# WS2811-Multi_Ver110_20211128.net
KiCad netlist of a schematic drawn in EAGLE
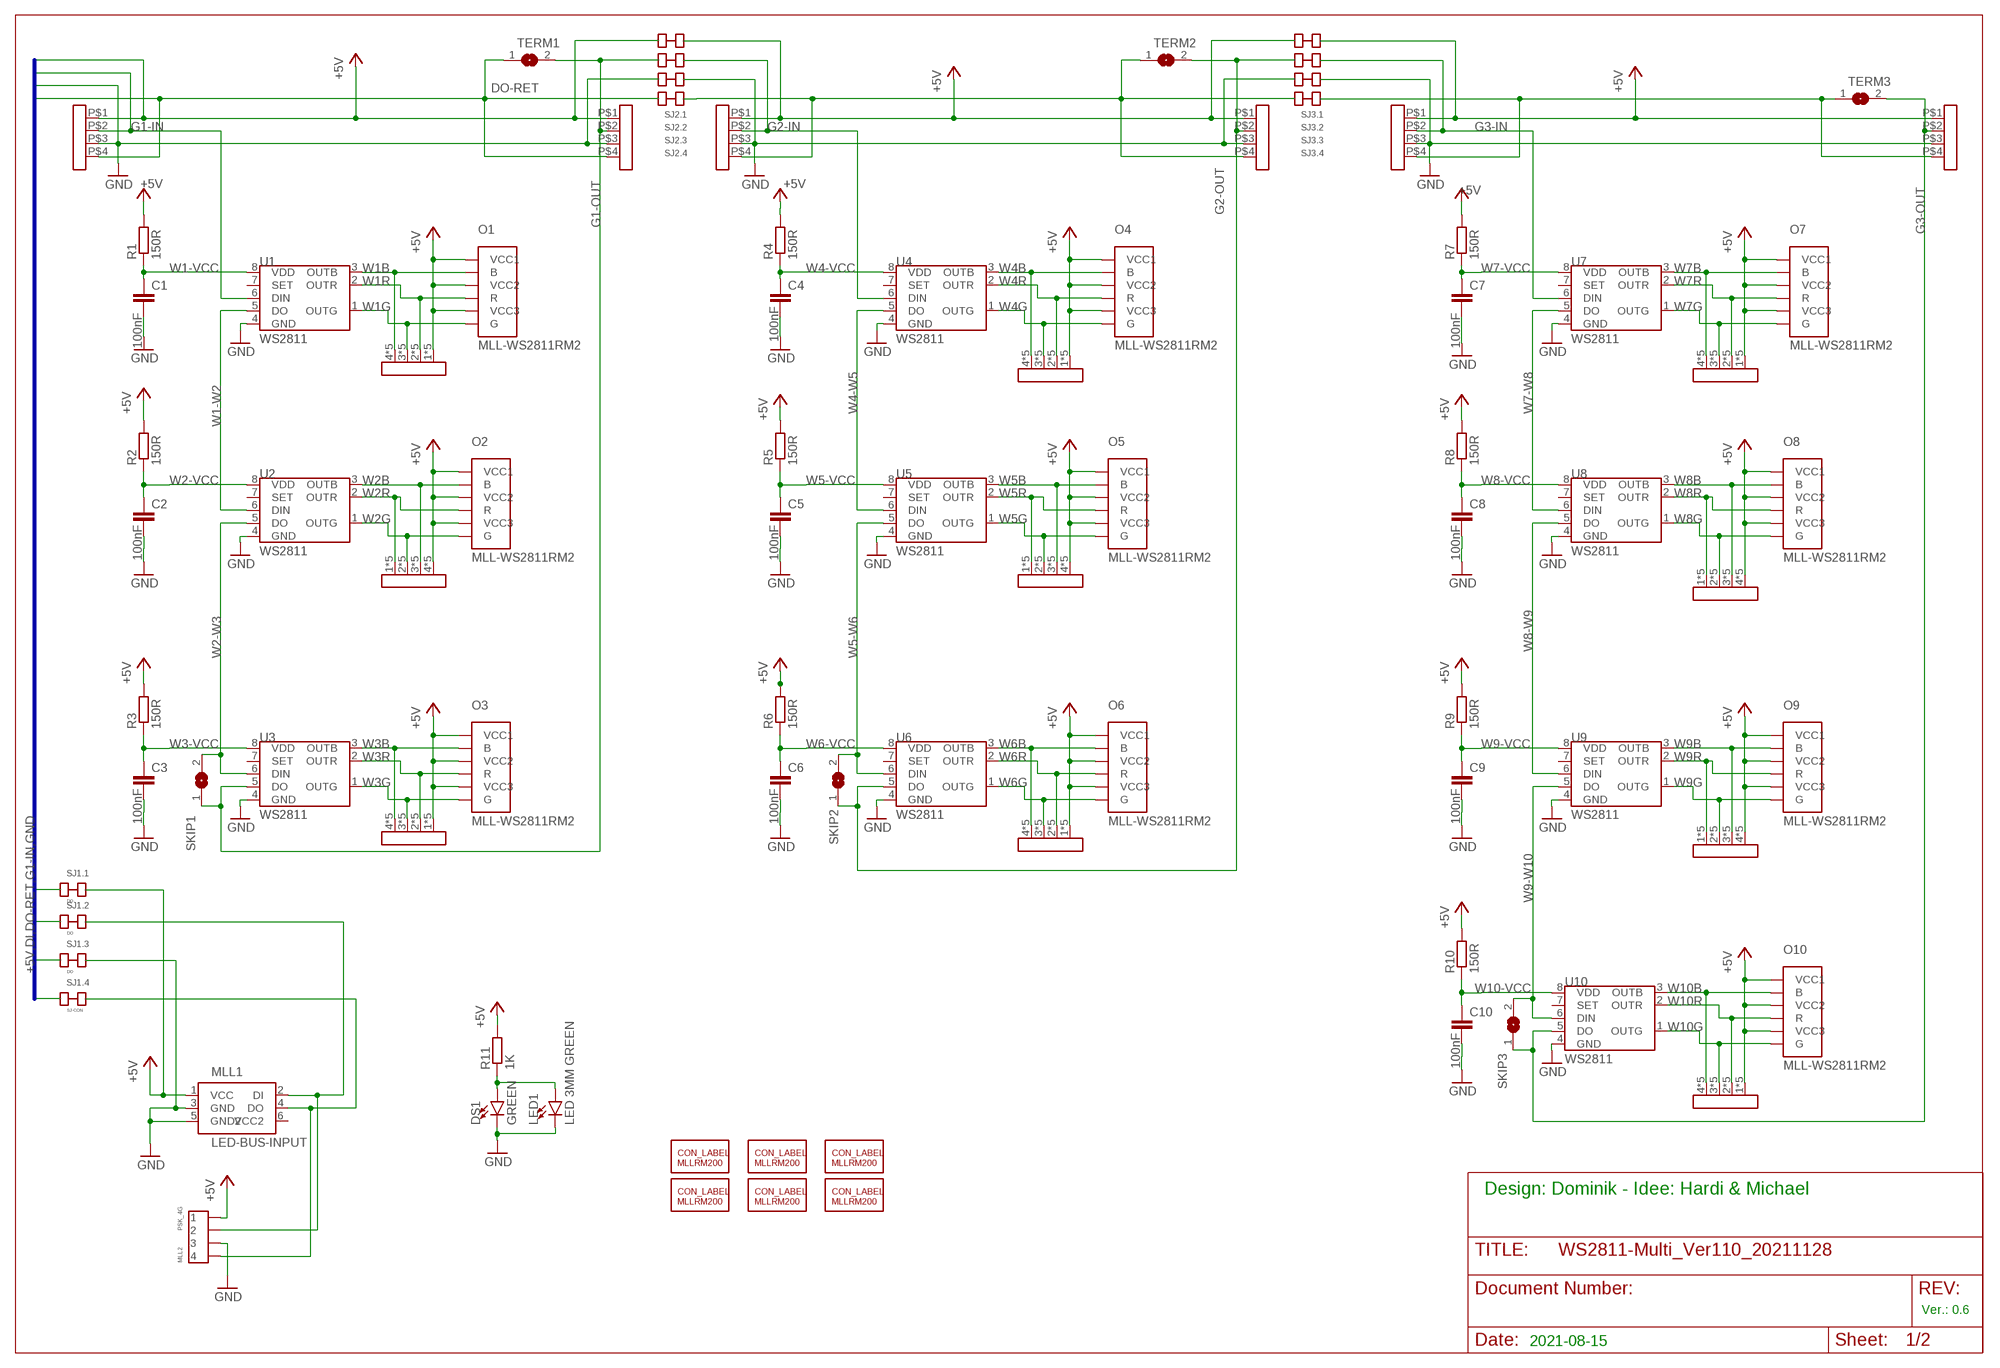
[diagram p0: schematic, sheet 1]
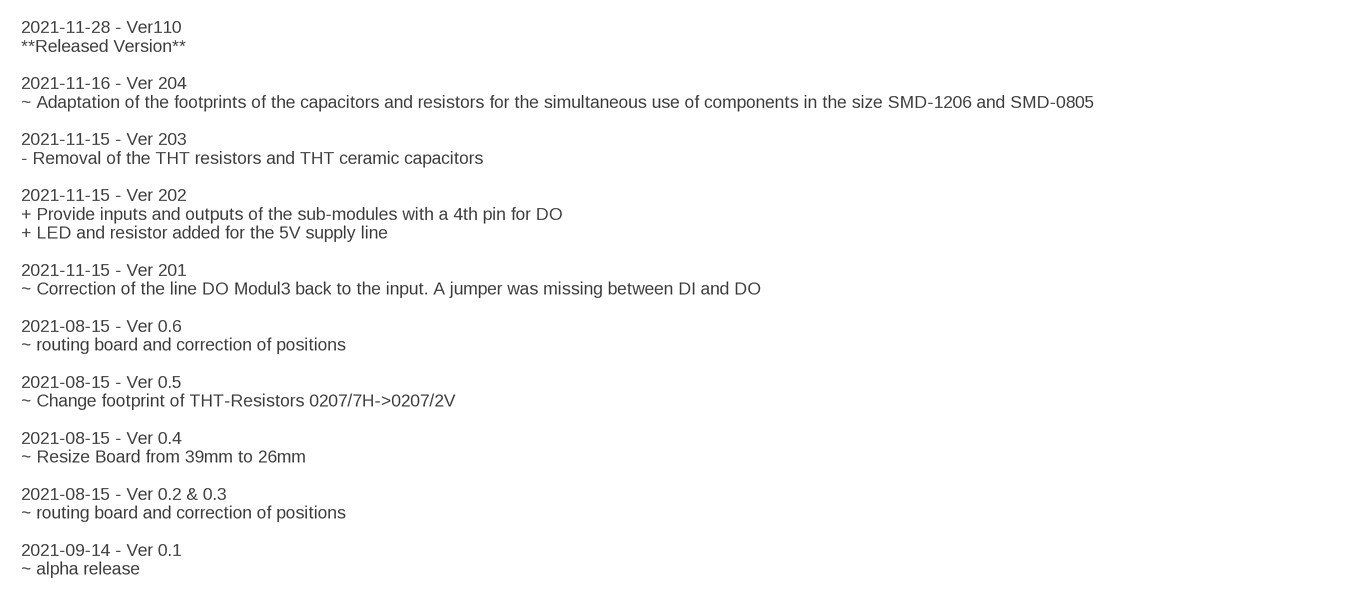
[diagram p1: schematic, sheet 2]

(export (version "E")
  (design (tool "Eeschema 10.0.6"))
  (components
    (comp (ref "C1")
      (value "100nF")
      (footprint "eagle-import:C1206")
      (libsource (lib "eagle-import") (part "C-EUC1206"))
    )
    (comp (ref "C2")
      (value "100nF")
      (footprint "eagle-import:C1206")
      (libsource (lib "eagle-import") (part "C-EUC1206"))
    )
    (comp (ref "C3")
      (value "100nF")
      (footprint "eagle-import:C1206")
      (libsource (lib "eagle-import") (part "C-EUC1206"))
    )
    (comp (ref "C4")
      (value "100nF")
      (footprint "eagle-import:C1206")
      (libsource (lib "eagle-import") (part "C-EUC1206"))
    )
    (comp (ref "C5")
      (value "100nF")
      (footprint "eagle-import:C1206")
      (libsource (lib "eagle-import") (part "C-EUC1206"))
    )
    (comp (ref "C6")
      (value "100nF")
      (footprint "eagle-import:C1206")
      (libsource (lib "eagle-import") (part "C-EUC1206"))
    )
    (comp (ref "C7")
      (value "100nF")
      (footprint "eagle-import:C1206")
      (libsource (lib "eagle-import") (part "C-EUC1206"))
    )
    (comp (ref "C8")
      (value "100nF")
      (footprint "eagle-import:C1206")
      (libsource (lib "eagle-import") (part "C-EUC1206"))
    )
    (comp (ref "C9")
      (value "100nF")
      (footprint "eagle-import:C1206")
      (libsource (lib "eagle-import") (part "C-EUC1206"))
    )
    (comp (ref "C10")
      (value "100nF")
      (footprint "eagle-import:C1206")
      (libsource (lib "eagle-import") (part "C-EUC1206"))
    )
    (comp (ref "DS1")
      (value "GREEN")
      (footprint "eagle-import:LED-1206")
      (libsource (lib "eagle-import") (part "LED-GREEN1206"))
    )
    (comp (ref "LED1")
      (value "LED 3MM GREEN")
      (footprint "eagle-import:LED_3MM")
      (libsource (lib "eagle-import") (part "LED3MM"))
    )
    (comp (ref "M1_IN")
      (value "4XRM254")
      (footprint "eagle-import:4XRM254")
      (libsource (lib "eagle-import") (part "4XRM254"))
    )
    (comp (ref "M1_OUT")
      (value "4XRM254")
      (footprint "eagle-import:4XRM254")
      (libsource (lib "eagle-import") (part "4XRM254"))
    )
    (comp (ref "M2_IN")
      (value "4XRM254")
      (footprint "eagle-import:4XRM254")
      (libsource (lib "eagle-import") (part "4XRM254"))
    )
    (comp (ref "M2_OUT")
      (value "4XRM254")
      (footprint "eagle-import:4XRM254")
      (libsource (lib "eagle-import") (part "4XRM254"))
    )
    (comp (ref "M3_IN")
      (value "4XRM254")
      (footprint "eagle-import:4XRM254")
      (libsource (lib "eagle-import") (part "4XRM254"))
    )
    (comp (ref "M3_OUT")
      (value "4XRM254")
      (footprint "eagle-import:4XRM254")
      (libsource (lib "eagle-import") (part "4XRM254"))
    )
    (comp (ref "MLL1")
      (value "LED-BUS-INPUT")
      (footprint "eagle-import:IDC6")
      (libsource (lib "eagle-import") (part "LED-BUS-INPUT"))
    )
    (comp (ref "MLL2")
      (value "PSK_4G")
      (footprint "eagle-import:PSSG4")
      (libsource (lib "eagle-import") (part "PSK_4G"))
    )
    (comp (ref "O1")
      (value "MLL-WS2811RM2")
      (footprint "eagle-import:MLL-WS2811-RM2")
      (libsource (lib "eagle-import") (part "MLL-WS2811RM2"))
    )
    (comp (ref "O2")
      (value "MLL-WS2811RM2")
      (footprint "eagle-import:MLL-WS2811-RM2")
      (libsource (lib "eagle-import") (part "MLL-WS2811RM2"))
    )
    (comp (ref "O3")
      (value "MLL-WS2811RM2")
      (footprint "eagle-import:MLL-WS2811-RM2")
      (libsource (lib "eagle-import") (part "MLL-WS2811RM2"))
    )
    (comp (ref "O4")
      (value "MLL-WS2811RM2")
      (footprint "eagle-import:MLL-WS2811-RM2")
      (libsource (lib "eagle-import") (part "MLL-WS2811RM2"))
    )
    (comp (ref "O5")
      (value "MLL-WS2811RM2")
      (footprint "eagle-import:MLL-WS2811-RM2")
      (libsource (lib "eagle-import") (part "MLL-WS2811RM2"))
    )
    (comp (ref "O6")
      (value "MLL-WS2811RM2")
      (footprint "eagle-import:MLL-WS2811-RM2")
      (libsource (lib "eagle-import") (part "MLL-WS2811RM2"))
    )
    (comp (ref "O7")
      (value "MLL-WS2811RM2")
      (footprint "eagle-import:MLL-WS2811-RM2")
      (libsource (lib "eagle-import") (part "MLL-WS2811RM2"))
    )
    (comp (ref "O8")
      (value "MLL-WS2811RM2")
      (footprint "eagle-import:MLL-WS2811-RM2")
      (libsource (lib "eagle-import") (part "MLL-WS2811RM2"))
    )
    (comp (ref "O9")
      (value "MLL-WS2811RM2")
      (footprint "eagle-import:MLL-WS2811-RM2")
      (libsource (lib "eagle-import") (part "MLL-WS2811RM2"))
    )
    (comp (ref "O10")
      (value "MLL-WS2811RM2")
      (footprint "eagle-import:MLL-WS2811-RM2")
      (libsource (lib "eagle-import") (part "MLL-WS2811RM2"))
    )
    (comp (ref "R1")
      (value "150R")
      (footprint "eagle-import:R1206")
      (libsource (lib "eagle-import") (part "R-EU_R1206"))
    )
    (comp (ref "R2")
      (value "150R")
      (footprint "eagle-import:R1206")
      (libsource (lib "eagle-import") (part "R-EU_R1206"))
    )
    (comp (ref "R3")
      (value "150R")
      (footprint "eagle-import:R1206")
      (libsource (lib "eagle-import") (part "R-EU_R1206"))
    )
    (comp (ref "R4")
      (value "150R")
      (footprint "eagle-import:R1206")
      (libsource (lib "eagle-import") (part "R-EU_R1206"))
    )
    (comp (ref "R5")
      (value "150R")
      (footprint "eagle-import:R1206")
      (libsource (lib "eagle-import") (part "R-EU_R1206"))
    )
    (comp (ref "R6")
      (value "150R")
      (footprint "eagle-import:R1206")
      (libsource (lib "eagle-import") (part "R-EU_R1206"))
    )
    (comp (ref "R7")
      (value "150R")
      (footprint "eagle-import:R1206")
      (libsource (lib "eagle-import") (part "R-EU_R1206"))
    )
    (comp (ref "R8")
      (value "150R")
      (footprint "eagle-import:R1206")
      (libsource (lib "eagle-import") (part "R-EU_R1206"))
    )
    (comp (ref "R9")
      (value "150R")
      (footprint "eagle-import:R1206")
      (libsource (lib "eagle-import") (part "R-EU_R1206"))
    )
    (comp (ref "R10")
      (value "150R")
      (footprint "eagle-import:R1206")
      (libsource (lib "eagle-import") (part "R-EU_R1206"))
    )
    (comp (ref "R11")
      (value "1K")
      (footprint "eagle-import:R1206")
      (libsource (lib "eagle-import") (part "R-EU_R1206"))
    )
    (comp (ref "SJ1.1")
      (value "DO")
      (footprint "eagle-import:SJ-CON")
      (libsource (lib "eagle-import") (part "SJ-CON"))
    )
    (comp (ref "SJ1.2")
      (value "DO")
      (footprint "eagle-import:SJ-CON")
      (libsource (lib "eagle-import") (part "SJ-CON"))
    )
    (comp (ref "SJ1.3")
      (value "DO")
      (footprint "eagle-import:SJ-CON")
      (libsource (lib "eagle-import") (part "SJ-CON"))
    )
    (comp (ref "SJ1.4")
      (value "SJ-CON")
      (footprint "eagle-import:SJ-CON")
      (libsource (lib "eagle-import") (part "SJ-CON"))
    )
    (comp (ref "SJ2.1")
      (value "SJ-CON")
      (footprint "eagle-import:SJ-CON")
      (libsource (lib "eagle-import") (part "SJ-CON"))
    )
    (comp (ref "SJ2.2")
      (value "SJ-CON")
      (footprint "eagle-import:SJ-CON")
      (libsource (lib "eagle-import") (part "SJ-CON"))
    )
    (comp (ref "SJ2.3")
      (value "SJ-CON")
      (footprint "eagle-import:SJ-CON")
      (libsource (lib "eagle-import") (part "SJ-CON"))
    )
    (comp (ref "SJ2.4")
      (value "SJ-CON")
      (footprint "eagle-import:SJ-CON")
      (libsource (lib "eagle-import") (part "SJ-CON"))
    )
    (comp (ref "SJ3.1")
      (value "SJ-CON")
      (footprint "eagle-import:SJ-CON")
      (libsource (lib "eagle-import") (part "SJ-CON"))
    )
    (comp (ref "SJ3.2")
      (value "SJ-CON")
      (footprint "eagle-import:SJ-CON")
      (libsource (lib "eagle-import") (part "SJ-CON"))
    )
    (comp (ref "SJ3.3")
      (value "SJ-CON")
      (footprint "eagle-import:SJ-CON")
      (libsource (lib "eagle-import") (part "SJ-CON"))
    )
    (comp (ref "SJ3.4")
      (value "SJ-CON")
      (footprint "eagle-import:SJ-CON")
      (libsource (lib "eagle-import") (part "SJ-CON"))
    )
    (comp (ref "SKIP1")
      (value "SJ")
      (footprint "eagle-import:SJ")
      (libsource (lib "eagle-import") (part "SJ"))
    )
    (comp (ref "SKIP2")
      (value "SJ")
      (footprint "eagle-import:SJ")
      (libsource (lib "eagle-import") (part "SJ"))
    )
    (comp (ref "SKIP3")
      (value "SJ")
      (footprint "eagle-import:SJ")
      (libsource (lib "eagle-import") (part "SJ"))
    )
    (comp (ref "TERM1")
      (value "SJ")
      (footprint "eagle-import:SJ")
      (libsource (lib "eagle-import") (part "SJ"))
    )
    (comp (ref "TERM2")
      (value "SJ")
      (footprint "eagle-import:SJ")
      (libsource (lib "eagle-import") (part "SJ"))
    )
    (comp (ref "TERM3")
      (value "SJ")
      (footprint "eagle-import:SJ")
      (libsource (lib "eagle-import") (part "SJ"))
    )
    (comp (ref "U$1")
      (value "CON-LABEL_MLLRM200_2RGB_M")
      (footprint "eagle-import:CON-LABEL_MLLRM200_RGB_M")
      (libsource (lib "eagle-import") (part "CON-LABEL_MLLRM200_2RGB_M"))
    )
    (comp (ref "U$2")
      (value "CON-LABEL_MLLRM200")
      (footprint "eagle-import:CON-LABEL_MLLRM200")
      (libsource (lib "eagle-import") (part "CON-LABEL_MLLRM200"))
    )
    (comp (ref "U$3")
      (value "CON-LABEL_MLLRM200_2RGB_M")
      (footprint "eagle-import:CON-LABEL_MLLRM200_RGB_M")
      (libsource (lib "eagle-import") (part "CON-LABEL_MLLRM200_2RGB_M"))
    )
    (comp (ref "U$4")
      (value "CON-LABEL_MLLRM200_2RGB_M")
      (footprint "eagle-import:CON-LABEL_MLLRM200_RGB_M")
      (libsource (lib "eagle-import") (part "CON-LABEL_MLLRM200_2RGB_M"))
    )
    (comp (ref "U$5")
      (value "CON-LABEL_MLLRM200_2RGB")
      (footprint "eagle-import:CON-LABEL_MLLRM200_RGB")
      (libsource (lib "eagle-import") (part "CON-LABEL_MLLRM200_2RGB"))
    )
    (comp (ref "U$6")
      (value "CON-LABEL_MLLRM200")
      (footprint "eagle-import:CON-LABEL_MLLRM200")
      (libsource (lib "eagle-import") (part "CON-LABEL_MLLRM200"))
    )
    (comp (ref "U$7")
      (value "4XRM200LONG-NOH_DOUBLE")
      (footprint "eagle-import:4XRM200LONG_NOH_DOUBLE")
      (libsource (lib "eagle-import") (part "4XRM200LONG-NOH_DOUBLE"))
    )
    (comp (ref "U$8")
      (value "4XRM200LONG-NOH_DOUBLE")
      (footprint "eagle-import:4XRM200LONG_NOH_DOUBLE")
      (libsource (lib "eagle-import") (part "4XRM200LONG-NOH_DOUBLE"))
    )
    (comp (ref "U$9")
      (value "4XRM200LONG-NOH_DOUBLE")
      (footprint "eagle-import:4XRM200LONG_NOH_DOUBLE")
      (libsource (lib "eagle-import") (part "4XRM200LONG-NOH_DOUBLE"))
    )
    (comp (ref "U$14")
      (value "4XRM200LONG-NOH_DOUBLE")
      (footprint "eagle-import:4XRM200LONG_NOH_DOUBLE")
      (libsource (lib "eagle-import") (part "4XRM200LONG-NOH_DOUBLE"))
    )
    (comp (ref "U$15")
      (value "4XRM200LONG-NOH_DOUBLE")
      (footprint "eagle-import:4XRM200LONG_NOH_DOUBLE")
      (libsource (lib "eagle-import") (part "4XRM200LONG-NOH_DOUBLE"))
    )
    (comp (ref "U$16")
      (value "4XRM200LONG-NOH_DOUBLE")
      (footprint "eagle-import:4XRM200LONG_NOH_DOUBLE")
      (libsource (lib "eagle-import") (part "4XRM200LONG-NOH_DOUBLE"))
    )
    (comp (ref "U$17")
      (value "4XRM200LONG-NOH_DOUBLE")
      (footprint "eagle-import:4XRM200LONG_NOH_DOUBLE")
      (libsource (lib "eagle-import") (part "4XRM200LONG-NOH_DOUBLE"))
    )
    (comp (ref "U$18")
      (value "4XRM200LONG-NOH_DOUBLE")
      (footprint "eagle-import:4XRM200LONG_NOH_DOUBLE")
      (libsource (lib "eagle-import") (part "4XRM200LONG-NOH_DOUBLE"))
    )
    (comp (ref "U$19")
      (value "4XRM200LONG-NOH_DOUBLE")
      (footprint "eagle-import:4XRM200LONG_NOH_DOUBLE")
      (libsource (lib "eagle-import") (part "4XRM200LONG-NOH_DOUBLE"))
    )
    (comp (ref "U$20")
      (value "4XRM200LONG-NOH_DOUBLE")
      (footprint "eagle-import:4XRM200LONG_NOH_DOUBLE")
      (libsource (lib "eagle-import") (part "4XRM200LONG-NOH_DOUBLE"))
    )
    (comp (ref "U1")
      (value "WS2811")
      (footprint "eagle-import:SOP8")
      (libsource (lib "eagle-import") (part "WS2811-ICSOP8"))
    )
    (comp (ref "U2")
      (value "WS2811")
      (footprint "eagle-import:SOP8")
      (libsource (lib "eagle-import") (part "WS2811-ICSOP8"))
    )
    (comp (ref "U3")
      (value "WS2811")
      (footprint "eagle-import:SOP8")
      (libsource (lib "eagle-import") (part "WS2811-ICSOP8"))
    )
    (comp (ref "U4")
      (value "WS2811")
      (footprint "eagle-import:SOP8")
      (libsource (lib "eagle-import") (part "WS2811-ICSOP8"))
    )
    (comp (ref "U5")
      (value "WS2811")
      (footprint "eagle-import:SOP8")
      (libsource (lib "eagle-import") (part "WS2811-ICSOP8"))
    )
    (comp (ref "U6")
      (value "WS2811")
      (footprint "eagle-import:SOP8")
      (libsource (lib "eagle-import") (part "WS2811-ICSOP8"))
    )
    (comp (ref "U7")
      (value "WS2811")
      (footprint "eagle-import:SOP8")
      (libsource (lib "eagle-import") (part "WS2811-ICSOP8"))
    )
    (comp (ref "U8")
      (value "WS2811")
      (footprint "eagle-import:SOP8")
      (libsource (lib "eagle-import") (part "WS2811-ICSOP8"))
    )
    (comp (ref "U9")
      (value "WS2811")
      (footprint "eagle-import:SOP8")
      (libsource (lib "eagle-import") (part "WS2811-ICSOP8"))
    )
    (comp (ref "U10")
      (value "WS2811")
      (footprint "eagle-import:SOP8")
      (libsource (lib "eagle-import") (part "WS2811-ICSOP8"))
    )
  )
  (nets
    (net (code "2") (name "+5V") (class "Default")
      (node (ref "M1_IN") (pin "P$1") (pinfunction "P$1_P$1") (pintype "bidirectional"))
      (node (ref "M1_OUT") (pin "P$1") (pinfunction "P$1_P$1") (pintype "bidirectional"))
      (node (ref "M2_IN") (pin "P$1") (pinfunction "P$1_P$1") (pintype "bidirectional"))
      (node (ref "M2_OUT") (pin "P$1") (pinfunction "P$1_P$1") (pintype "bidirectional"))
      (node (ref "M3_IN") (pin "P$1") (pinfunction "P$1_P$1") (pintype "bidirectional"))
      (node (ref "M3_OUT") (pin "P$1") (pinfunction "P$1_P$1") (pintype "bidirectional"))
      (node (ref "MLL1") (pin "1") (pinfunction "VCC_1") (pintype "power_in"))
      (node (ref "MLL2") (pin "P$1") (pinfunction "1_P$1") (pintype "bidirectional"))
      (node (ref "O1") (pin "VCC1") (pinfunction "VCC1_VCC1") (pintype "bidirectional"))
      (node (ref "O1") (pin "VCC2") (pinfunction "VCC2_VCC2") (pintype "bidirectional"))
      (node (ref "O1") (pin "VCC3") (pinfunction "VCC3_VCC3") (pintype "bidirectional"))
      (node (ref "O10") (pin "VCC1") (pinfunction "VCC1_VCC1") (pintype "bidirectional"))
      (node (ref "O10") (pin "VCC2") (pinfunction "VCC2_VCC2") (pintype "bidirectional"))
      (node (ref "O10") (pin "VCC3") (pinfunction "VCC3_VCC3") (pintype "bidirectional"))
      (node (ref "O2") (pin "VCC1") (pinfunction "VCC1_VCC1") (pintype "bidirectional"))
      (node (ref "O2") (pin "VCC2") (pinfunction "VCC2_VCC2") (pintype "bidirectional"))
      (node (ref "O2") (pin "VCC3") (pinfunction "VCC3_VCC3") (pintype "bidirectional"))
      (node (ref "O3") (pin "VCC1") (pinfunction "VCC1_VCC1") (pintype "bidirectional"))
      (node (ref "O3") (pin "VCC2") (pinfunction "VCC2_VCC2") (pintype "bidirectional"))
      (node (ref "O3") (pin "VCC3") (pinfunction "VCC3_VCC3") (pintype "bidirectional"))
      (node (ref "O4") (pin "VCC1") (pinfunction "VCC1_VCC1") (pintype "bidirectional"))
      (node (ref "O4") (pin "VCC2") (pinfunction "VCC2_VCC2") (pintype "bidirectional"))
      (node (ref "O4") (pin "VCC3") (pinfunction "VCC3_VCC3") (pintype "bidirectional"))
      (node (ref "O5") (pin "VCC1") (pinfunction "VCC1_VCC1") (pintype "bidirectional"))
      (node (ref "O5") (pin "VCC2") (pinfunction "VCC2_VCC2") (pintype "bidirectional"))
      (node (ref "O5") (pin "VCC3") (pinfunction "VCC3_VCC3") (pintype "bidirectional"))
      (node (ref "O6") (pin "VCC1") (pinfunction "VCC1_VCC1") (pintype "bidirectional"))
      (node (ref "O6") (pin "VCC2") (pinfunction "VCC2_VCC2") (pintype "bidirectional"))
      (node (ref "O6") (pin "VCC3") (pinfunction "VCC3_VCC3") (pintype "bidirectional"))
      (node (ref "O7") (pin "VCC1") (pinfunction "VCC1_VCC1") (pintype "bidirectional"))
      (node (ref "O7") (pin "VCC2") (pinfunction "VCC2_VCC2") (pintype "bidirectional"))
      (node (ref "O7") (pin "VCC3") (pinfunction "VCC3_VCC3") (pintype "bidirectional"))
      (node (ref "O8") (pin "VCC1") (pinfunction "VCC1_VCC1") (pintype "bidirectional"))
      (node (ref "O8") (pin "VCC2") (pinfunction "VCC2_VCC2") (pintype "bidirectional"))
      (node (ref "O8") (pin "VCC3") (pinfunction "VCC3_VCC3") (pintype "bidirectional"))
      (node (ref "O9") (pin "VCC1") (pinfunction "VCC1_VCC1") (pintype "bidirectional"))
      (node (ref "O9") (pin "VCC2") (pinfunction "VCC2_VCC2") (pintype "bidirectional"))
      (node (ref "O9") (pin "VCC3") (pinfunction "VCC3_VCC3") (pintype "bidirectional"))
      (node (ref "R1") (pin "2") (pinfunction "2_2") (pintype "passive"))
      (node (ref "R10") (pin "2") (pinfunction "2_2") (pintype "passive"))
      (node (ref "R11") (pin "2") (pinfunction "2_2") (pintype "passive"))
      (node (ref "R2") (pin "2") (pinfunction "2_2") (pintype "passive"))
      (node (ref "R3") (pin "2") (pinfunction "2_2") (pintype "passive"))
      (node (ref "R4") (pin "2") (pinfunction "2_2") (pintype "passive"))
      (node (ref "R5") (pin "2") (pinfunction "2_2") (pintype "passive"))
      (node (ref "R6") (pin "2") (pinfunction "2_2") (pintype "passive"))
      (node (ref "R7") (pin "2") (pinfunction "2_2") (pintype "passive"))
      (node (ref "R8") (pin "2") (pinfunction "2_2") (pintype "passive"))
      (node (ref "R9") (pin "2") (pinfunction "2_2") (pintype "passive"))
      (node (ref "SJ1.1") (pin "P$1") (pinfunction "P$1_P$1") (pintype "bidirectional"))
      (node (ref "SJ1.1") (pin "P$2") (pinfunction "P$2_P$2") (pintype "bidirectional"))
      (node (ref "SJ2.1") (pin "P$1") (pinfunction "P$1_P$1") (pintype "bidirectional"))
      (node (ref "SJ2.1") (pin "P$2") (pinfunction "P$2_P$2") (pintype "bidirectional"))
      (node (ref "SJ3.1") (pin "P$1") (pinfunction "P$1_P$1") (pintype "bidirectional"))
      (node (ref "SJ3.1") (pin "P$2") (pinfunction "P$2_P$2") (pintype "bidirectional"))
      (node (ref "U$14") (pin "1") (pinfunction "P$1_1") (pintype "bidirectional"))
      (node (ref "U$14") (pin "11") (pinfunction "P$1_11") (pintype "bidirectional"))
      (node (ref "U$14") (pin "12") (pinfunction "P$1_12") (pintype "bidirectional"))
      (node (ref "U$14") (pin "13") (pinfunction "P$1_13") (pintype "bidirectional"))
      (node (ref "U$14") (pin "1B") (pinfunction "P$1_1B") (pintype "bidirectional"))
      (node (ref "U$15") (pin "4") (pinfunction "P$4_4") (pintype "bidirectional"))
      (node (ref "U$15") (pin "41") (pinfunction "P$4_41") (pintype "bidirectional"))
      (node (ref "U$15") (pin "42") (pinfunction "P$4_42") (pintype "bidirectional"))
      (node (ref "U$15") (pin "43") (pinfunction "P$4_43") (pintype "bidirectional"))
      (node (ref "U$15") (pin "4B") (pinfunction "P$4_4B") (pintype "bidirectional"))
      (node (ref "U$16") (pin "1") (pinfunction "P$1_1") (pintype "bidirectional"))
      (node (ref "U$16") (pin "11") (pinfunction "P$1_11") (pintype "bidirectional"))
      (node (ref "U$16") (pin "12") (pinfunction "P$1_12") (pintype "bidirectional"))
      (node (ref "U$16") (pin "13") (pinfunction "P$1_13") (pintype "bidirectional"))
      (node (ref "U$16") (pin "1B") (pinfunction "P$1_1B") (pintype "bidirectional"))
      (node (ref "U$17") (pin "1") (pinfunction "P$1_1") (pintype "bidirectional"))
      (node (ref "U$17") (pin "11") (pinfunction "P$1_11") (pintype "bidirectional"))
      (node (ref "U$17") (pin "12") (pinfunction "P$1_12") (pintype "bidirectional"))
      (node (ref "U$17") (pin "13") (pinfunction "P$1_13") (pintype "bidirectional"))
      (node (ref "U$17") (pin "1B") (pinfunction "P$1_1B") (pintype "bidirectional"))
      (node (ref "U$18") (pin "4") (pinfunction "P$4_4") (pintype "bidirectional"))
      (node (ref "U$18") (pin "41") (pinfunction "P$4_41") (pintype "bidirectional"))
      (node (ref "U$18") (pin "42") (pinfunction "P$4_42") (pintype "bidirectional"))
      (node (ref "U$18") (pin "43") (pinfunction "P$4_43") (pintype "bidirectional"))
      (node (ref "U$18") (pin "4B") (pinfunction "P$4_4B") (pintype "bidirectional"))
      (node (ref "U$19") (pin "4") (pinfunction "P$4_4") (pintype "bidirectional"))
      (node (ref "U$19") (pin "41") (pinfunction "P$4_41") (pintype "bidirectional"))
      (node (ref "U$19") (pin "42") (pinfunction "P$4_42") (pintype "bidirectional"))
      (node (ref "U$19") (pin "43") (pinfunction "P$4_43") (pintype "bidirectional"))
      (node (ref "U$19") (pin "4B") (pinfunction "P$4_4B") (pintype "bidirectional"))
      (node (ref "U$20") (pin "1") (pinfunction "P$1_1") (pintype "bidirectional"))
      (node (ref "U$20") (pin "11") (pinfunction "P$1_11") (pintype "bidirectional"))
      (node (ref "U$20") (pin "12") (pinfunction "P$1_12") (pintype "bidirectional"))
      (node (ref "U$20") (pin "13") (pinfunction "P$1_13") (pintype "bidirectional"))
      (node (ref "U$20") (pin "1B") (pinfunction "P$1_1B") (pintype "bidirectional"))
      (node (ref "U$7") (pin "1") (pinfunction "P$1_1") (pintype "bidirectional"))
      (node (ref "U$7") (pin "11") (pinfunction "P$1_11") (pintype "bidirectional"))
      (node (ref "U$7") (pin "12") (pinfunction "P$1_12") (pintype "bidirectional"))
      (node (ref "U$7") (pin "13") (pinfunction "P$1_13") (pintype "bidirectional"))
      (node (ref "U$7") (pin "1B") (pinfunction "P$1_1B") (pintype "bidirectional"))
      (node (ref "U$8") (pin "4") (pinfunction "P$4_4") (pintype "bidirectional"))
      (node (ref "U$8") (pin "41") (pinfunction "P$4_41") (pintype "bidirectional"))
      (node (ref "U$8") (pin "42") (pinfunction "P$4_42") (pintype "bidirectional"))
      (node (ref "U$8") (pin "43") (pinfunction "P$4_43") (pintype "bidirectional"))
      (node (ref "U$8") (pin "4B") (pinfunction "P$4_4B") (pintype "bidirectional"))
      (node (ref "U$9") (pin "1") (pinfunction "P$1_1") (pintype "bidirectional"))
      (node (ref "U$9") (pin "11") (pinfunction "P$1_11") (pintype "bidirectional"))
      (node (ref "U$9") (pin "12") (pinfunction "P$1_12") (pintype "bidirectional"))
      (node (ref "U$9") (pin "13") (pinfunction "P$1_13") (pintype "bidirectional"))
      (node (ref "U$9") (pin "1B") (pinfunction "P$1_1B") (pintype "bidirectional"))
    )
    (net (code "4") (name "DO-RET") (class "Default")
      (node (ref "M1_IN") (pin "P$4") (pinfunction "P$4_P$4") (pintype "bidirectional"))
      (node (ref "M1_OUT") (pin "P$4") (pinfunction "P$4_P$4") (pintype "bidirectional"))
      (node (ref "SJ1.4") (pin "P$1") (pinfunction "P$1_P$1") (pintype "bidirectional"))
      (node (ref "SJ2.4") (pin "P$1") (pinfunction "P$1_P$1") (pintype "bidirectional"))
      (node (ref "TERM1") (pin "1") (pinfunction "1_1") (pintype "passive"))
    )
    (net (code "5") (name "G1-IN") (class "Default")
      (node (ref "M1_IN") (pin "P$2") (pinfunction "P$2_P$2") (pintype "bidirectional"))
      (node (ref "SJ1.2") (pin "P$1") (pinfunction "P$1_P$1") (pintype "bidirectional"))
      (node (ref "U1") (pin "6") (pinfunction "DIN_6") (pintype "input"))
    )
    (net (code "6") (name "G1-OUT") (class "Default")
      (node (ref "M1_OUT") (pin "P$2") (pinfunction "P$2_P$2") (pintype "bidirectional"))
      (node (ref "SJ2.2") (pin "P$1") (pinfunction "P$1_P$1") (pintype "bidirectional"))
      (node (ref "SKIP1") (pin "1") (pinfunction "1_1") (pintype "passive"))
      (node (ref "TERM1") (pin "2") (pinfunction "2_2") (pintype "passive"))
      (node (ref "U3") (pin "5") (pinfunction "DO_5") (pintype "output"))
    )
    (net (code "7") (name "G2-IN") (class "Default")
      (node (ref "M2_IN") (pin "P$2") (pinfunction "P$2_P$2") (pintype "bidirectional"))
      (node (ref "SJ2.2") (pin "P$2") (pinfunction "P$2_P$2") (pintype "bidirectional"))
      (node (ref "U4") (pin "6") (pinfunction "DIN_6") (pintype "input"))
    )
    (net (code "8") (name "G2-OUT") (class "Default")
      (node (ref "M2_OUT") (pin "P$2") (pinfunction "P$2_P$2") (pintype "bidirectional"))
      (node (ref "SJ3.2") (pin "P$1") (pinfunction "P$1_P$1") (pintype "bidirectional"))
      (node (ref "SKIP2") (pin "1") (pinfunction "1_1") (pintype "passive"))
      (node (ref "TERM2") (pin "2") (pinfunction "2_2") (pintype "passive"))
      (node (ref "U6") (pin "5") (pinfunction "DO_5") (pintype "output"))
    )
    (net (code "9") (name "G3-IN") (class "Default")
      (node (ref "M3_IN") (pin "P$2") (pinfunction "P$2_P$2") (pintype "bidirectional"))
      (node (ref "SJ3.2") (pin "P$2") (pinfunction "P$2_P$2") (pintype "bidirectional"))
      (node (ref "U7") (pin "6") (pinfunction "DIN_6") (pintype "input"))
    )
    (net (code "10") (name "G3-OUT") (class "Default")
      (node (ref "M3_OUT") (pin "P$2") (pinfunction "P$2_P$2") (pintype "bidirectional"))
      (node (ref "SKIP3") (pin "1") (pinfunction "1_1") (pintype "passive"))
      (node (ref "TERM3") (pin "2") (pinfunction "2_2") (pintype "passive"))
      (node (ref "U10") (pin "5") (pinfunction "DO_5") (pintype "output"))
    )
    (net (code "11") (name "GND") (class "Default")
      (node (ref "C1") (pin "2") (pinfunction "2_2") (pintype "passive"))
      (node (ref "C10") (pin "2") (pinfunction "2_2") (pintype "passive"))
      (node (ref "C2") (pin "2") (pinfunction "2_2") (pintype "passive"))
      (node (ref "C3") (pin "2") (pinfunction "2_2") (pintype "passive"))
      (node (ref "C4") (pin "2") (pinfunction "2_2") (pintype "passive"))
      (node (ref "C5") (pin "2") (pinfunction "2_2") (pintype "passive"))
      (node (ref "C6") (pin "2") (pinfunction "2_2") (pintype "passive"))
      (node (ref "C7") (pin "2") (pinfunction "2_2") (pintype "passive"))
      (node (ref "C8") (pin "2") (pinfunction "2_2") (pintype "passive"))
      (node (ref "C9") (pin "2") (pinfunction "2_2") (pintype "passive"))
      (node (ref "DS1") (pin "C") (pinfunction "C_C") (pintype "passive"))
      (node (ref "LED1") (pin "K") (pinfunction "C_K") (pintype "passive"))
      (node (ref "M1_IN") (pin "P$3") (pinfunction "P$3_P$3") (pintype "bidirectional"))
      (node (ref "M1_OUT") (pin "P$3") (pinfunction "P$3_P$3") (pintype "bidirectional"))
      (node (ref "M2_IN") (pin "P$3") (pinfunction "P$3_P$3") (pintype "bidirectional"))
      (node (ref "M2_OUT") (pin "P$3") (pinfunction "P$3_P$3") (pintype "bidirectional"))
      (node (ref "M3_IN") (pin "P$3") (pinfunction "P$3_P$3") (pintype "bidirectional"))
      (node (ref "M3_OUT") (pin "P$3") (pinfunction "P$3_P$3") (pintype "bidirectional"))
      (node (ref "MLL1") (pin "3") (pinfunction "GND_3") (pintype "power_in"))
      (node (ref "MLL1") (pin "5") (pinfunction "GND2_5") (pintype "power_in"))
      (node (ref "MLL2") (pin "P$3") (pinfunction "3_P$3") (pintype "bidirectional"))
      (node (ref "SJ1.3") (pin "P$1") (pinfunction "P$1_P$1") (pintype "bidirectional"))
      (node (ref "SJ1.3") (pin "P$2") (pinfunction "P$2_P$2") (pintype "bidirectional"))
      (node (ref "SJ2.3") (pin "P$1") (pinfunction "P$1_P$1") (pintype "bidirectional"))
      (node (ref "SJ2.3") (pin "P$2") (pinfunction "P$2_P$2") (pintype "bidirectional"))
      (node (ref "SJ3.3") (pin "P$1") (pinfunction "P$1_P$1") (pintype "bidirectional"))
      (node (ref "SJ3.3") (pin "P$2") (pinfunction "P$2_P$2") (pintype "bidirectional"))
      (node (ref "U1") (pin "4") (pinfunction "GND_4") (pintype "power_in"))
      (node (ref "U10") (pin "4") (pinfunction "GND_4") (pintype "power_in"))
      (node (ref "U2") (pin "4") (pinfunction "GND_4") (pintype "power_in"))
      (node (ref "U3") (pin "4") (pinfunction "GND_4") (pintype "power_in"))
      (node (ref "U4") (pin "4") (pinfunction "GND_4") (pintype "power_in"))
      (node (ref "U5") (pin "4") (pinfunction "GND_4") (pintype "power_in"))
      (node (ref "U6") (pin "4") (pinfunction "GND_4") (pintype "power_in"))
      (node (ref "U7") (pin "4") (pinfunction "GND_4") (pintype "power_in"))
      (node (ref "U8") (pin "4") (pinfunction "GND_4") (pintype "power_in"))
      (node (ref "U9") (pin "4") (pinfunction "GND_4") (pintype "power_in"))
    )
    (net (code "12") (name "Net-(DS1-PadA)") (class "Default")
      (node (ref "DS1") (pin "A") (pinfunction "A_A") (pintype "passive"))
      (node (ref "LED1") (pin "A") (pinfunction "A_A") (pintype "passive"))
      (node (ref "R11") (pin "1") (pinfunction "1_1") (pintype "passive"))
    )
    (net (code "13") (name "Net-(M2_IN-PadP$4)") (class "Default")
      (node (ref "M2_IN") (pin "P$4") (pinfunction "P$4_P$4") (pintype "bidirectional"))
      (node (ref "M2_OUT") (pin "P$4") (pinfunction "P$4_P$4") (pintype "bidirectional"))
      (node (ref "SJ2.4") (pin "P$2") (pinfunction "P$2_P$2") (pintype "bidirectional"))
      (node (ref "SJ3.4") (pin "P$1") (pinfunction "P$1_P$1") (pintype "bidirectional"))
      (node (ref "TERM2") (pin "1") (pinfunction "1_1") (pintype "passive"))
    )
    (net (code "14") (name "Net-(M3_IN-PadP$4)") (class "Default")
      (node (ref "M3_IN") (pin "P$4") (pinfunction "P$4_P$4") (pintype "bidirectional"))
      (node (ref "M3_OUT") (pin "P$4") (pinfunction "P$4_P$4") (pintype "bidirectional"))
      (node (ref "SJ3.4") (pin "P$2") (pinfunction "P$2_P$2") (pintype "bidirectional"))
      (node (ref "TERM3") (pin "1") (pinfunction "1_1") (pintype "passive"))
    )
    (net (code "15") (name "Net-(MLL1-DI)") (class "Default")
      (node (ref "MLL1") (pin "2") (pinfunction "DI_2") (pintype "input"))
      (node (ref "MLL2") (pin "P$2") (pinfunction "2_P$2") (pintype "bidirectional"))
      (node (ref "SJ1.2") (pin "P$2") (pinfunction "P$2_P$2") (pintype "bidirectional"))
    )
    (net (code "16") (name "Net-(MLL1-DO)") (class "Default")
      (node (ref "MLL1") (pin "4") (pinfunction "DO_4") (pintype "output"))
      (node (ref "MLL2") (pin "P$4") (pinfunction "4_P$4") (pintype "bidirectional"))
      (node (ref "SJ1.4") (pin "P$2") (pinfunction "P$2_P$2") (pintype "bidirectional"))
    )
    (net (code "17") (name "VCC2") (class "Default")
      (node (ref "MLL1") (pin "6") (pinfunction "VCC2_6") (pintype "power_in"))
    )
    (net (code "18") (name "W1-VCC") (class "Default")
      (node (ref "C1") (pin "1") (pinfunction "1_1") (pintype "passive"))
      (node (ref "R1") (pin "1") (pinfunction "1_1") (pintype "passive"))
      (node (ref "U1") (pin "8") (pinfunction "VDD_8") (pintype "power_in"))
    )
    (net (code "19") (name "W1-W2") (class "Default")
      (node (ref "U1") (pin "5") (pinfunction "DO_5") (pintype "output"))
      (node (ref "U2") (pin "6") (pinfunction "DIN_6") (pintype "input"))
    )
    (net (code "20") (name "W1B") (class "Default")
      (node (ref "O1") (pin "B") (pinfunction "B_B") (pintype "bidirectional"))
      (node (ref "U$9") (pin "4") (pinfunction "P$4_4") (pintype "bidirectional"))
      (node (ref "U$9") (pin "41") (pinfunction "P$4_41") (pintype "bidirectional"))
      (node (ref "U$9") (pin "42") (pinfunction "P$4_42") (pintype "bidirectional"))
      (node (ref "U$9") (pin "43") (pinfunction "P$4_43") (pintype "bidirectional"))
      (node (ref "U$9") (pin "4B") (pinfunction "P$4_4B") (pintype "bidirectional"))
      (node (ref "U1") (pin "3") (pinfunction "OUTB_3") (pintype "open_collector"))
    )
    (net (code "21") (name "W1G") (class "Default")
      (node (ref "O1") (pin "G") (pinfunction "G_G") (pintype "bidirectional"))
      (node (ref "U$9") (pin "3") (pinfunction "P$3_3") (pintype "bidirectional"))
      (node (ref "U$9") (pin "31") (pinfunction "P$3_31") (pintype "bidirectional"))
      (node (ref "U$9") (pin "32") (pinfunction "P$3_32") (pintype "bidirectional"))
      (node (ref "U$9") (pin "33") (pinfunction "P$3_33") (pintype "bidirectional"))
      (node (ref "U$9") (pin "3B") (pinfunction "P$3_3B") (pintype "bidirectional"))
      (node (ref "U1") (pin "1") (pinfunction "OUTG_1") (pintype "open_collector"))
    )
    (net (code "22") (name "W1R") (class "Default")
      (node (ref "O1") (pin "R") (pinfunction "R_R") (pintype "bidirectional"))
      (node (ref "U$9") (pin "2") (pinfunction "P$2_2") (pintype "bidirectional"))
      (node (ref "U$9") (pin "21") (pinfunction "P$2_21") (pintype "bidirectional"))
      (node (ref "U$9") (pin "22") (pinfunction "P$2_22") (pintype "bidirectional"))
      (node (ref "U$9") (pin "23") (pinfunction "P$2_23") (pintype "bidirectional"))
      (node (ref "U$9") (pin "2B") (pinfunction "P$2_2B") (pintype "bidirectional"))
      (node (ref "U1") (pin "2") (pinfunction "OUTR_2") (pintype "open_collector"))
    )
    (net (code "23") (name "W2-VCC") (class "Default")
      (node (ref "C2") (pin "1") (pinfunction "1_1") (pintype "passive"))
      (node (ref "R2") (pin "1") (pinfunction "1_1") (pintype "passive"))
      (node (ref "U2") (pin "8") (pinfunction "VDD_8") (pintype "power_in"))
    )
    (net (code "24") (name "W2-W3") (class "Default")
      (node (ref "SKIP1") (pin "2") (pinfunction "2_2") (pintype "passive"))
      (node (ref "U2") (pin "5") (pinfunction "DO_5") (pintype "output"))
      (node (ref "U3") (pin "6") (pinfunction "DIN_6") (pintype "input"))
    )
    (net (code "25") (name "W2B") (class "Default")
      (node (ref "O2") (pin "B") (pinfunction "B_B") (pintype "bidirectional"))
      (node (ref "U$8") (pin "3") (pinfunction "P$3_3") (pintype "bidirectional"))
      (node (ref "U$8") (pin "31") (pinfunction "P$3_31") (pintype "bidirectional"))
      (node (ref "U$8") (pin "32") (pinfunction "P$3_32") (pintype "bidirectional"))
      (node (ref "U$8") (pin "33") (pinfunction "P$3_33") (pintype "bidirectional"))
      (node (ref "U$8") (pin "3B") (pinfunction "P$3_3B") (pintype "bidirectional"))
      (node (ref "U2") (pin "3") (pinfunction "OUTB_3") (pintype "open_collector"))
    )
    (net (code "26") (name "W2G") (class "Default")
      (node (ref "O2") (pin "G") (pinfunction "G_G") (pintype "bidirectional"))
      (node (ref "U$8") (pin "2") (pinfunction "P$2_2") (pintype "bidirectional"))
      (node (ref "U$8") (pin "21") (pinfunction "P$2_21") (pintype "bidirectional"))
      (node (ref "U$8") (pin "22") (pinfunction "P$2_22") (pintype "bidirectional"))
      (node (ref "U$8") (pin "23") (pinfunction "P$2_23") (pintype "bidirectional"))
      (node (ref "U$8") (pin "2B") (pinfunction "P$2_2B") (pintype "bidirectional"))
      (node (ref "U2") (pin "1") (pinfunction "OUTG_1") (pintype "open_collector"))
    )
    (net (code "27") (name "W2R") (class "Default")
      (node (ref "O2") (pin "R") (pinfunction "R_R") (pintype "bidirectional"))
      (node (ref "U$8") (pin "1") (pinfunction "P$1_1") (pintype "bidirectional"))
      (node (ref "U$8") (pin "11") (pinfunction "P$1_11") (pintype "bidirectional"))
      (node (ref "U$8") (pin "12") (pinfunction "P$1_12") (pintype "bidirectional"))
      (node (ref "U$8") (pin "13") (pinfunction "P$1_13") (pintype "bidirectional"))
      (node (ref "U$8") (pin "1B") (pinfunction "P$1_1B") (pintype "bidirectional"))
      (node (ref "U2") (pin "2") (pinfunction "OUTR_2") (pintype "open_collector"))
    )
    (net (code "28") (name "W3-VCC") (class "Default")
      (node (ref "C3") (pin "1") (pinfunction "1_1") (pintype "passive"))
      (node (ref "R3") (pin "1") (pinfunction "1_1") (pintype "passive"))
      (node (ref "U3") (pin "8") (pinfunction "VDD_8") (pintype "power_in"))
    )
    (net (code "29") (name "W3B") (class "Default")
      (node (ref "O3") (pin "B") (pinfunction "B_B") (pintype "bidirectional"))
      (node (ref "U$7") (pin "4") (pinfunction "P$4_4") (pintype "bidirectional"))
      (node (ref "U$7") (pin "41") (pinfunction "P$4_41") (pintype "bidirectional"))
      (node (ref "U$7") (pin "42") (pinfunction "P$4_42") (pintype "bidirectional"))
      (node (ref "U$7") (pin "43") (pinfunction "P$4_43") (pintype "bidirectional"))
      (node (ref "U$7") (pin "4B") (pinfunction "P$4_4B") (pintype "bidirectional"))
      (node (ref "U3") (pin "3") (pinfunction "OUTB_3") (pintype "open_collector"))
    )
    (net (code "30") (name "W3G") (class "Default")
      (node (ref "O3") (pin "G") (pinfunction "G_G") (pintype "bidirectional"))
      (node (ref "U$7") (pin "3") (pinfunction "P$3_3") (pintype "bidirectional"))
      (node (ref "U$7") (pin "31") (pinfunction "P$3_31") (pintype "bidirectional"))
      (node (ref "U$7") (pin "32") (pinfunction "P$3_32") (pintype "bidirectional"))
      (node (ref "U$7") (pin "33") (pinfunction "P$3_33") (pintype "bidirectional"))
      (node (ref "U$7") (pin "3B") (pinfunction "P$3_3B") (pintype "bidirectional"))
      (node (ref "U3") (pin "1") (pinfunction "OUTG_1") (pintype "open_collector"))
    )
    (net (code "31") (name "W3R") (class "Default")
      (node (ref "O3") (pin "R") (pinfunction "R_R") (pintype "bidirectional"))
      (node (ref "U$7") (pin "2") (pinfunction "P$2_2") (pintype "bidirectional"))
      (node (ref "U$7") (pin "21") (pinfunction "P$2_21") (pintype "bidirectional"))
      (node (ref "U$7") (pin "22") (pinfunction "P$2_22") (pintype "bidirectional"))
      (node (ref "U$7") (pin "23") (pinfunction "P$2_23") (pintype "bidirectional"))
      (node (ref "U$7") (pin "2B") (pinfunction "P$2_2B") (pintype "bidirectional"))
      (node (ref "U3") (pin "2") (pinfunction "OUTR_2") (pintype "open_collector"))
    )
    (net (code "32") (name "W4-VCC") (class "Default")
      (node (ref "C4") (pin "1") (pinfunction "1_1") (pintype "passive"))
      (node (ref "R4") (pin "1") (pinfunction "1_1") (pintype "passive"))
      (node (ref "U4") (pin "8") (pinfunction "VDD_8") (pintype "power_in"))
    )
    (net (code "33") (name "W4-W5") (class "Default")
      (node (ref "U4") (pin "5") (pinfunction "DO_5") (pintype "output"))
      (node (ref "U5") (pin "6") (pinfunction "DIN_6") (pintype "input"))
    )
    (net (code "34") (name "W4B") (class "Default")
      (node (ref "O4") (pin "B") (pinfunction "B_B") (pintype "bidirectional"))
      (node (ref "U$14") (pin "4") (pinfunction "P$4_4") (pintype "bidirectional"))
      (node (ref "U$14") (pin "41") (pinfunction "P$4_41") (pintype "bidirectional"))
      (node (ref "U$14") (pin "42") (pinfunction "P$4_42") (pintype "bidirectional"))
      (node (ref "U$14") (pin "43") (pinfunction "P$4_43") (pintype "bidirectional"))
      (node (ref "U$14") (pin "4B") (pinfunction "P$4_4B") (pintype "bidirectional"))
      (node (ref "U4") (pin "3") (pinfunction "OUTB_3") (pintype "open_collector"))
    )
    (net (code "35") (name "W4G") (class "Default")
      (node (ref "O4") (pin "G") (pinfunction "G_G") (pintype "bidirectional"))
      (node (ref "U$14") (pin "3") (pinfunction "P$3_3") (pintype "bidirectional"))
      (node (ref "U$14") (pin "31") (pinfunction "P$3_31") (pintype "bidirectional"))
      (node (ref "U$14") (pin "32") (pinfunction "P$3_32") (pintype "bidirectional"))
      (node (ref "U$14") (pin "33") (pinfunction "P$3_33") (pintype "bidirectional"))
      (node (ref "U$14") (pin "3B") (pinfunction "P$3_3B") (pintype "bidirectional"))
      (node (ref "U4") (pin "1") (pinfunction "OUTG_1") (pintype "open_collector"))
    )
    (net (code "36") (name "W4R") (class "Default")
      (node (ref "O4") (pin "R") (pinfunction "R_R") (pintype "bidirectional"))
      (node (ref "U$14") (pin "2") (pinfunction "P$2_2") (pintype "bidirectional"))
      (node (ref "U$14") (pin "21") (pinfunction "P$2_21") (pintype "bidirectional"))
      (node (ref "U$14") (pin "22") (pinfunction "P$2_22") (pintype "bidirectional"))
      (node (ref "U$14") (pin "23") (pinfunction "P$2_23") (pintype "bidirectional"))
      (node (ref "U$14") (pin "2B") (pinfunction "P$2_2B") (pintype "bidirectional"))
      (node (ref "U4") (pin "2") (pinfunction "OUTR_2") (pintype "open_collector"))
    )
    (net (code "37") (name "W5-VCC") (class "Default")
      (node (ref "C5") (pin "1") (pinfunction "1_1") (pintype "passive"))
      (node (ref "R5") (pin "1") (pinfunction "1_1") (pintype "passive"))
      (node (ref "U5") (pin "8") (pinfunction "VDD_8") (pintype "power_in"))
    )
    (net (code "38") (name "W5-W6") (class "Default")
      (node (ref "SKIP2") (pin "2") (pinfunction "2_2") (pintype "passive"))
      (node (ref "U5") (pin "5") (pinfunction "DO_5") (pintype "output"))
      (node (ref "U6") (pin "6") (pinfunction "DIN_6") (pintype "input"))
    )
    (net (code "39") (name "W5B") (class "Default")
      (node (ref "O5") (pin "B") (pinfunction "B_B") (pintype "bidirectional"))
      (node (ref "U$15") (pin "3") (pinfunction "P$3_3") (pintype "bidirectional"))
      (node (ref "U$15") (pin "31") (pinfunction "P$3_31") (pintype "bidirectional"))
      (node (ref "U$15") (pin "32") (pinfunction "P$3_32") (pintype "bidirectional"))
      (node (ref "U$15") (pin "33") (pinfunction "P$3_33") (pintype "bidirectional"))
      (node (ref "U$15") (pin "3B") (pinfunction "P$3_3B") (pintype "bidirectional"))
      (node (ref "U5") (pin "3") (pinfunction "OUTB_3") (pintype "open_collector"))
    )
    (net (code "40") (name "W5G") (class "Default")
      (node (ref "O5") (pin "G") (pinfunction "G_G") (pintype "bidirectional"))
      (node (ref "U$15") (pin "2") (pinfunction "P$2_2") (pintype "bidirectional"))
      (node (ref "U$15") (pin "21") (pinfunction "P$2_21") (pintype "bidirectional"))
      (node (ref "U$15") (pin "22") (pinfunction "P$2_22") (pintype "bidirectional"))
      (node (ref "U$15") (pin "23") (pinfunction "P$2_23") (pintype "bidirectional"))
      (node (ref "U$15") (pin "2B") (pinfunction "P$2_2B") (pintype "bidirectional"))
      (node (ref "U5") (pin "1") (pinfunction "OUTG_1") (pintype "open_collector"))
    )
    (net (code "41") (name "W5R") (class "Default")
      (node (ref "O5") (pin "R") (pinfunction "R_R") (pintype "bidirectional"))
      (node (ref "U$15") (pin "1") (pinfunction "P$1_1") (pintype "bidirectional"))
      (node (ref "U$15") (pin "11") (pinfunction "P$1_11") (pintype "bidirectional"))
      (node (ref "U$15") (pin "12") (pinfunction "P$1_12") (pintype "bidirectional"))
      (node (ref "U$15") (pin "13") (pinfunction "P$1_13") (pintype "bidirectional"))
      (node (ref "U$15") (pin "1B") (pinfunction "P$1_1B") (pintype "bidirectional"))
      (node (ref "U5") (pin "2") (pinfunction "OUTR_2") (pintype "open_collector"))
    )
    (net (code "42") (name "W6-VCC") (class "Default")
      (node (ref "C6") (pin "1") (pinfunction "1_1") (pintype "passive"))
      (node (ref "R6") (pin "1") (pinfunction "1_1") (pintype "passive"))
      (node (ref "U6") (pin "8") (pinfunction "VDD_8") (pintype "power_in"))
    )
    (net (code "43") (name "W6B") (class "Default")
      (node (ref "O6") (pin "B") (pinfunction "B_B") (pintype "bidirectional"))
      (node (ref "U$16") (pin "4") (pinfunction "P$4_4") (pintype "bidirectional"))
      (node (ref "U$16") (pin "41") (pinfunction "P$4_41") (pintype "bidirectional"))
      (node (ref "U$16") (pin "42") (pinfunction "P$4_42") (pintype "bidirectional"))
      (node (ref "U$16") (pin "43") (pinfunction "P$4_43") (pintype "bidirectional"))
      (node (ref "U$16") (pin "4B") (pinfunction "P$4_4B") (pintype "bidirectional"))
      (node (ref "U6") (pin "3") (pinfunction "OUTB_3") (pintype "open_collector"))
    )
    (net (code "44") (name "W6G") (class "Default")
      (node (ref "O6") (pin "G") (pinfunction "G_G") (pintype "bidirectional"))
      (node (ref "U$16") (pin "3") (pinfunction "P$3_3") (pintype "bidirectional"))
      (node (ref "U$16") (pin "31") (pinfunction "P$3_31") (pintype "bidirectional"))
      (node (ref "U$16") (pin "32") (pinfunction "P$3_32") (pintype "bidirectional"))
      (node (ref "U$16") (pin "33") (pinfunction "P$3_33") (pintype "bidirectional"))
      (node (ref "U$16") (pin "3B") (pinfunction "P$3_3B") (pintype "bidirectional"))
      (node (ref "U6") (pin "1") (pinfunction "OUTG_1") (pintype "open_collector"))
    )
    (net (code "45") (name "W6R") (class "Default")
      (node (ref "O6") (pin "R") (pinfunction "R_R") (pintype "bidirectional"))
      (node (ref "U$16") (pin "2") (pinfunction "P$2_2") (pintype "bidirectional"))
      (node (ref "U$16") (pin "21") (pinfunction "P$2_21") (pintype "bidirectional"))
      (node (ref "U$16") (pin "22") (pinfunction "P$2_22") (pintype "bidirectional"))
      (node (ref "U$16") (pin "23") (pinfunction "P$2_23") (pintype "bidirectional"))
      (node (ref "U$16") (pin "2B") (pinfunction "P$2_2B") (pintype "bidirectional"))
      (node (ref "U6") (pin "2") (pinfunction "OUTR_2") (pintype "open_collector"))
    )
    (net (code "46") (name "W7-VCC") (class "Default")
      (node (ref "C7") (pin "1") (pinfunction "1_1") (pintype "passive"))
      (node (ref "R7") (pin "1") (pinfunction "1_1") (pintype "passive"))
      (node (ref "U7") (pin "8") (pinfunction "VDD_8") (pintype "power_in"))
    )
    (net (code "47") (name "W7-W8") (class "Default")
      (node (ref "U7") (pin "5") (pinfunction "DO_5") (pintype "output"))
      (node (ref "U8") (pin "6") (pinfunction "DIN_6") (pintype "input"))
    )
    (net (code "48") (name "W7B") (class "Default")
      (node (ref "O7") (pin "B") (pinfunction "B_B") (pintype "bidirectional"))
      (node (ref "U$17") (pin "4") (pinfunction "P$4_4") (pintype "bidirectional"))
      (node (ref "U$17") (pin "41") (pinfunction "P$4_41") (pintype "bidirectional"))
      (node (ref "U$17") (pin "42") (pinfunction "P$4_42") (pintype "bidirectional"))
      (node (ref "U$17") (pin "43") (pinfunction "P$4_43") (pintype "bidirectional"))
      (node (ref "U$17") (pin "4B") (pinfunction "P$4_4B") (pintype "bidirectional"))
      (node (ref "U7") (pin "3") (pinfunction "OUTB_3") (pintype "open_collector"))
    )
    (net (code "49") (name "W7G") (class "Default")
      (node (ref "O7") (pin "G") (pinfunction "G_G") (pintype "bidirectional"))
      (node (ref "U$17") (pin "3") (pinfunction "P$3_3") (pintype "bidirectional"))
      (node (ref "U$17") (pin "31") (pinfunction "P$3_31") (pintype "bidirectional"))
      (node (ref "U$17") (pin "32") (pinfunction "P$3_32") (pintype "bidirectional"))
      (node (ref "U$17") (pin "33") (pinfunction "P$3_33") (pintype "bidirectional"))
      (node (ref "U$17") (pin "3B") (pinfunction "P$3_3B") (pintype "bidirectional"))
      (node (ref "U7") (pin "1") (pinfunction "OUTG_1") (pintype "open_collector"))
    )
    (net (code "50") (name "W7R") (class "Default")
      (node (ref "O7") (pin "R") (pinfunction "R_R") (pintype "bidirectional"))
      (node (ref "U$17") (pin "2") (pinfunction "P$2_2") (pintype "bidirectional"))
      (node (ref "U$17") (pin "21") (pinfunction "P$2_21") (pintype "bidirectional"))
      (node (ref "U$17") (pin "22") (pinfunction "P$2_22") (pintype "bidirectional"))
      (node (ref "U$17") (pin "23") (pinfunction "P$2_23") (pintype "bidirectional"))
      (node (ref "U$17") (pin "2B") (pinfunction "P$2_2B") (pintype "bidirectional"))
      (node (ref "U7") (pin "2") (pinfunction "OUTR_2") (pintype "open_collector"))
    )
    (net (code "51") (name "W8-VCC") (class "Default")
      (node (ref "C8") (pin "1") (pinfunction "1_1") (pintype "passive"))
      (node (ref "R8") (pin "1") (pinfunction "1_1") (pintype "passive"))
      (node (ref "U8") (pin "8") (pinfunction "VDD_8") (pintype "power_in"))
    )
    (net (code "52") (name "W8-W9") (class "Default")
      (node (ref "U8") (pin "5") (pinfunction "DO_5") (pintype "output"))
      (node (ref "U9") (pin "6") (pinfunction "DIN_6") (pintype "input"))
    )
    (net (code "53") (name "W8B") (class "Default")
      (node (ref "O8") (pin "B") (pinfunction "B_B") (pintype "bidirectional"))
      (node (ref "U$18") (pin "3") (pinfunction "P$3_3") (pintype "bidirectional"))
      (node (ref "U$18") (pin "31") (pinfunction "P$3_31") (pintype "bidirectional"))
      (node (ref "U$18") (pin "32") (pinfunction "P$3_32") (pintype "bidirectional"))
      (node (ref "U$18") (pin "33") (pinfunction "P$3_33") (pintype "bidirectional"))
      (node (ref "U$18") (pin "3B") (pinfunction "P$3_3B") (pintype "bidirectional"))
      (node (ref "U8") (pin "3") (pinfunction "OUTB_3") (pintype "open_collector"))
    )
    (net (code "54") (name "W8G") (class "Default")
      (node (ref "O8") (pin "G") (pinfunction "G_G") (pintype "bidirectional"))
      (node (ref "U$18") (pin "2") (pinfunction "P$2_2") (pintype "bidirectional"))
      (node (ref "U$18") (pin "21") (pinfunction "P$2_21") (pintype "bidirectional"))
      (node (ref "U$18") (pin "22") (pinfunction "P$2_22") (pintype "bidirectional"))
      (node (ref "U$18") (pin "23") (pinfunction "P$2_23") (pintype "bidirectional"))
      (node (ref "U$18") (pin "2B") (pinfunction "P$2_2B") (pintype "bidirectional"))
      (node (ref "U8") (pin "1") (pinfunction "OUTG_1") (pintype "open_collector"))
    )
    (net (code "55") (name "W8R") (class "Default")
      (node (ref "O8") (pin "R") (pinfunction "R_R") (pintype "bidirectional"))
      (node (ref "U$18") (pin "1") (pinfunction "P$1_1") (pintype "bidirectional"))
      (node (ref "U$18") (pin "11") (pinfunction "P$1_11") (pintype "bidirectional"))
      (node (ref "U$18") (pin "12") (pinfunction "P$1_12") (pintype "bidirectional"))
      (node (ref "U$18") (pin "13") (pinfunction "P$1_13") (pintype "bidirectional"))
      (node (ref "U$18") (pin "1B") (pinfunction "P$1_1B") (pintype "bidirectional"))
      (node (ref "U8") (pin "2") (pinfunction "OUTR_2") (pintype "open_collector"))
    )
    (net (code "56") (name "W9-VCC") (class "Default")
      (node (ref "C9") (pin "1") (pinfunction "1_1") (pintype "passive"))
      (node (ref "R9") (pin "1") (pinfunction "1_1") (pintype "passive"))
      (node (ref "U9") (pin "8") (pinfunction "VDD_8") (pintype "power_in"))
    )
    (net (code "57") (name "W9-W10") (class "Default")
      (node (ref "SKIP3") (pin "2") (pinfunction "2_2") (pintype "passive"))
      (node (ref "U10") (pin "6") (pinfunction "DIN_6") (pintype "input"))
      (node (ref "U9") (pin "5") (pinfunction "DO_5") (pintype "output"))
    )
    (net (code "58") (name "W9B") (class "Default")
      (node (ref "O9") (pin "B") (pinfunction "B_B") (pintype "bidirectional"))
      (node (ref "U$19") (pin "3") (pinfunction "P$3_3") (pintype "bidirectional"))
      (node (ref "U$19") (pin "31") (pinfunction "P$3_31") (pintype "bidirectional"))
      (node (ref "U$19") (pin "32") (pinfunction "P$3_32") (pintype "bidirectional"))
      (node (ref "U$19") (pin "33") (pinfunction "P$3_33") (pintype "bidirectional"))
      (node (ref "U$19") (pin "3B") (pinfunction "P$3_3B") (pintype "bidirectional"))
      (node (ref "U9") (pin "3") (pinfunction "OUTB_3") (pintype "open_collector"))
    )
    (net (code "59") (name "W9G") (class "Default")
      (node (ref "O9") (pin "G") (pinfunction "G_G") (pintype "bidirectional"))
      (node (ref "U$19") (pin "2") (pinfunction "P$2_2") (pintype "bidirectional"))
      (node (ref "U$19") (pin "21") (pinfunction "P$2_21") (pintype "bidirectional"))
      (node (ref "U$19") (pin "22") (pinfunction "P$2_22") (pintype "bidirectional"))
      (node (ref "U$19") (pin "23") (pinfunction "P$2_23") (pintype "bidirectional"))
      (node (ref "U$19") (pin "2B") (pinfunction "P$2_2B") (pintype "bidirectional"))
      (node (ref "U9") (pin "1") (pinfunction "OUTG_1") (pintype "open_collector"))
    )
    (net (code "60") (name "W9R") (class "Default")
      (node (ref "O9") (pin "R") (pinfunction "R_R") (pintype "bidirectional"))
      (node (ref "U$19") (pin "1") (pinfunction "P$1_1") (pintype "bidirectional"))
      (node (ref "U$19") (pin "11") (pinfunction "P$1_11") (pintype "bidirectional"))
      (node (ref "U$19") (pin "12") (pinfunction "P$1_12") (pintype "bidirectional"))
      (node (ref "U$19") (pin "13") (pinfunction "P$1_13") (pintype "bidirectional"))
      (node (ref "U$19") (pin "1B") (pinfunction "P$1_1B") (pintype "bidirectional"))
      (node (ref "U9") (pin "2") (pinfunction "OUTR_2") (pintype "open_collector"))
    )
    (net (code "61") (name "W10-VCC") (class "Default")
      (node (ref "C10") (pin "1") (pinfunction "1_1") (pintype "passive"))
      (node (ref "R10") (pin "1") (pinfunction "1_1") (pintype "passive"))
      (node (ref "U10") (pin "8") (pinfunction "VDD_8") (pintype "power_in"))
    )
    (net (code "62") (name "W10B") (class "Default")
      (node (ref "O10") (pin "B") (pinfunction "B_B") (pintype "bidirectional"))
      (node (ref "U$20") (pin "4") (pinfunction "P$4_4") (pintype "bidirectional"))
      (node (ref "U$20") (pin "41") (pinfunction "P$4_41") (pintype "bidirectional"))
      (node (ref "U$20") (pin "42") (pinfunction "P$4_42") (pintype "bidirectional"))
      (node (ref "U$20") (pin "43") (pinfunction "P$4_43") (pintype "bidirectional"))
      (node (ref "U$20") (pin "4B") (pinfunction "P$4_4B") (pintype "bidirectional"))
      (node (ref "U10") (pin "3") (pinfunction "OUTB_3") (pintype "open_collector"))
    )
    (net (code "63") (name "W10G") (class "Default")
      (node (ref "O10") (pin "G") (pinfunction "G_G") (pintype "bidirectional"))
      (node (ref "U$20") (pin "3") (pinfunction "P$3_3") (pintype "bidirectional"))
      (node (ref "U$20") (pin "31") (pinfunction "P$3_31") (pintype "bidirectional"))
      (node (ref "U$20") (pin "32") (pinfunction "P$3_32") (pintype "bidirectional"))
      (node (ref "U$20") (pin "33") (pinfunction "P$3_33") (pintype "bidirectional"))
      (node (ref "U$20") (pin "3B") (pinfunction "P$3_3B") (pintype "bidirectional"))
      (node (ref "U10") (pin "1") (pinfunction "OUTG_1") (pintype "open_collector"))
    )
    (net (code "64") (name "W10R") (class "Default")
      (node (ref "O10") (pin "R") (pinfunction "R_R") (pintype "bidirectional"))
      (node (ref "U$20") (pin "2") (pinfunction "P$2_2") (pintype "bidirectional"))
      (node (ref "U$20") (pin "21") (pinfunction "P$2_21") (pintype "bidirectional"))
      (node (ref "U$20") (pin "22") (pinfunction "P$2_22") (pintype "bidirectional"))
      (node (ref "U$20") (pin "23") (pinfunction "P$2_23") (pintype "bidirectional"))
      (node (ref "U$20") (pin "2B") (pinfunction "P$2_2B") (pintype "bidirectional"))
      (node (ref "U10") (pin "2") (pinfunction "OUTR_2") (pintype "open_collector"))
    )
    (net (code "65") (name "unconnected-(U1-SET-Pad7)") (class "Default")
      (node (ref "U1") (pin "7") (pinfunction "SET_7") (pintype "bidirectional"))
    )
    (net (code "66") (name "unconnected-(U2-SET-Pad7)") (class "Default")
      (node (ref "U2") (pin "7") (pinfunction "SET_7") (pintype "bidirectional"))
    )
    (net (code "67") (name "unconnected-(U3-SET-Pad7)") (class "Default")
      (node (ref "U3") (pin "7") (pinfunction "SET_7") (pintype "bidirectional"))
    )
    (net (code "68") (name "unconnected-(U4-SET-Pad7)") (class "Default")
      (node (ref "U4") (pin "7") (pinfunction "SET_7") (pintype "bidirectional"))
    )
    (net (code "69") (name "unconnected-(U5-SET-Pad7)") (class "Default")
      (node (ref "U5") (pin "7") (pinfunction "SET_7") (pintype "bidirectional"))
    )
    (net (code "70") (name "unconnected-(U6-SET-Pad7)") (class "Default")
      (node (ref "U6") (pin "7") (pinfunction "SET_7") (pintype "bidirectional"))
    )
    (net (code "71") (name "unconnected-(U7-SET-Pad7)") (class "Default")
      (node (ref "U7") (pin "7") (pinfunction "SET_7") (pintype "bidirectional"))
    )
    (net (code "72") (name "unconnected-(U8-SET-Pad7)") (class "Default")
      (node (ref "U8") (pin "7") (pinfunction "SET_7") (pintype "bidirectional"))
    )
    (net (code "73") (name "unconnected-(U9-SET-Pad7)") (class "Default")
      (node (ref "U9") (pin "7") (pinfunction "SET_7") (pintype "bidirectional"))
    )
    (net (code "74") (name "unconnected-(U10-SET-Pad7)") (class "Default")
      (node (ref "U10") (pin "7") (pinfunction "SET_7") (pintype "bidirectional"))
    )
  )
)
